# M24512-DFMC6TG.net
KiCad netlist of a schematic drawn in Altium Designer
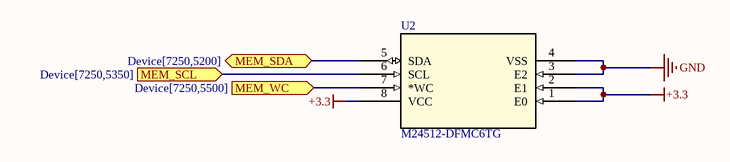
[diagram p0: M24512-DFMC6TG.SchDoc]

(export (version "E")
  (design (tool "Eeschema 10.0.6"))
  (components
    (comp (ref "U2")
      (value "M24512-DFMC6TG")
      (footprint "M24512-DFMC6TG")
      (libsource (lib "ReadyButNotListed") (part "M24512-DFMC6TG"))
    )
  )
  (nets
    (net (code "1") (name "+3.3") (class "Default")
      (node (ref "U2") (pin "1") (pinfunction "E0_1") (pintype "input"))
      (node (ref "U2") (pin "2") (pinfunction "E1_2") (pintype "input"))
      (node (ref "U2") (pin "8") (pinfunction "VCC_8") (pintype "power_in"))
    )
    (net (code "2") (name "/MEM_SCL") (class "Default")
      (node (ref "U2") (pin "6") (pinfunction "SCL_6") (pintype "input"))
    )
    (net (code "3") (name "/MEM_SDA") (class "Default")
      (node (ref "U2") (pin "5") (pinfunction "SDA_5") (pintype "bidirectional"))
    )
    (net (code "4") (name "/MEM_WC") (class "Default")
      (node (ref "U2") (pin "7") (pinfunction "*WC_7") (pintype "input"))
    )
    (net (code "5") (name "GND") (class "Default")
      (node (ref "U2") (pin "3") (pinfunction "E2_3") (pintype "input"))
      (node (ref "U2") (pin "4") (pinfunction "VSS_4") (pintype "passive"))
    )
  )
)
